# design.net
KiCad netlist of a schematic drawn in Altium Designer
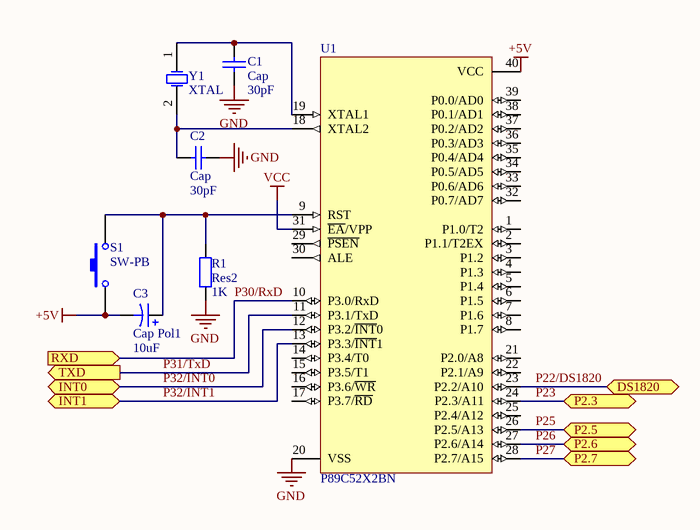
[diagram p0: 最小系统.SchDoc]

(export (version "E")
  (design (tool "Eeschema 10.0.6"))
  (components
    (comp (ref "C1")
      (value "Cap")
      (footprint "RAD-0.3")
      (description "Capacitor")
      (fields (field (name "ALTIUM_VALUE") "30pF") (field (name "PUBLISHER") "Altium Limited"))
      (libsource (lib "Miscellaneous Devices") (part "Cap"))
    )
    (comp (ref "C2")
      (value "Cap")
      (footprint "RAD-0.3")
      (description "Capacitor")
      (fields (field (name "ALTIUM_VALUE") "30pF") (field (name "PUBLISHER") "Altium Limited"))
      (libsource (lib "Miscellaneous Devices") (part "Cap"))
    )
    (comp (ref "C3")
      (value "Cap Pol1")
      (footprint "RB7.6-15")
      (description "Polarized Capacitor (Radial)")
      (fields (field (name "ALTIUM_VALUE") "10uF") (field (name "PUBLISHER") "Altium Limited"))
      (libsource (lib "Miscellaneous Devices") (part "Cap Pol1"))
    )
    (comp (ref "R1")
      (value "Res2")
      (footprint "AXIAL-0.4")
      (description "Resistor")
      (fields (field (name "ALTIUM_VALUE") "1K") (field (name "PUBLISHER") "Altium Limited"))
      (libsource (lib "Miscellaneous Devices") (part "Res2"))
    )
    (comp (ref "S1")
      (value "SW-PB")
      (footprint "SPST-2")
      (description "Switch")
      (fields (field (name "PUBLISHER") "Altium Limited"))
      (libsource (lib "Miscellaneous Devices") (part "SW-PB"))
    )
    (comp (ref "U1")
      (value "P89C52X2BN")
      (footprint "SOT129-1")
      (description "80C51 8-Bit Flash Microcontroller Family, 8 kB Flash")
      (fields (field (name "PUBLISHER") "Altium Limited"))
      (libsource (lib "Philips Microcontroller 8-Bit") (part "P89C52X2BN"))
    )
    (comp (ref "Y1")
      (value "XTAL")
      (footprint "R38")
      (description "Crystal Oscillator")
      (fields (field (name "PUBLISHER") "Altium Limited"))
      (libsource (lib "Miscellaneous Devices") (part "XTAL"))
    )
  )
  (nets
    (net (code "1") (name "+5V") (class "Default")
      (node (ref "C3") (pin "2") (pinfunction "2_2") (pintype "passive"))
      (node (ref "S1") (pin "1") (pinfunction "1_1") (pintype "passive"))
      (node (ref "U1") (pin "40") (pinfunction "VCC_40") (pintype "power_in"))
    )
    (net (code "2") (name "/P22{slash}DS1820") (class "Default")
      (node (ref "U1") (pin "23") (pinfunction "P2.2/A10_23") (pintype "bidirectional"))
    )
    (net (code "3") (name "/P23") (class "Default")
      (node (ref "U1") (pin "24") (pinfunction "P2.3/A11_24") (pintype "bidirectional"))
    )
    (net (code "4") (name "/P25") (class "Default")
      (node (ref "U1") (pin "26") (pinfunction "P2.5/A13_26") (pintype "bidirectional"))
    )
    (net (code "5") (name "/P26") (class "Default")
      (node (ref "U1") (pin "27") (pinfunction "P2.6/A14_27") (pintype "bidirectional"))
    )
    (net (code "6") (name "/P27") (class "Default")
      (node (ref "U1") (pin "28") (pinfunction "P2.7/A15_28") (pintype "bidirectional"))
    )
    (net (code "7") (name "/P30{slash}RxD") (class "Default")
      (node (ref "U1") (pin "10") (pinfunction "P3.0/RxD_10") (pintype "bidirectional"))
    )
    (net (code "8") (name "/P31{slash}TxD") (class "Default")
      (node (ref "U1") (pin "11") (pinfunction "P3.1/TxD_11") (pintype "bidirectional"))
    )
    (net (code "9") (name "/P32{slash}INT0") (class "Default")
      (node (ref "U1") (pin "12") (pinfunction "P3.2/~{INT}0_12") (pintype "bidirectional"))
    )
    (net (code "10") (name "/P32{slash}INT1") (class "Default")
      (node (ref "U1") (pin "13") (pinfunction "P3.3/~{INT}1_13") (pintype "bidirectional"))
    )
    (net (code "11") (name "GND") (class "Default")
      (node (ref "C1") (pin "1") (pinfunction "1_1") (pintype "passive"))
      (node (ref "C2") (pin "1") (pinfunction "1_1") (pintype "passive"))
      (node (ref "R1") (pin "1") (pinfunction "1_1") (pintype "passive"))
      (node (ref "U1") (pin "20") (pinfunction "VSS_20") (pintype "power_in"))
    )
    (net (code "12") (name "Net-(U1-RST)") (class "Default")
      (node (ref "C3") (pin "1") (pinfunction "1_1") (pintype "passive"))
      (node (ref "R1") (pin "2") (pinfunction "2_2") (pintype "passive"))
      (node (ref "S1") (pin "2") (pinfunction "2_2") (pintype "passive"))
      (node (ref "U1") (pin "9") (pinfunction "RST_9") (pintype "input"))
    )
    (net (code "13") (name "Net-(U1-XTAL1)") (class "Default")
      (node (ref "C1") (pin "2") (pinfunction "2_2") (pintype "passive"))
      (node (ref "U1") (pin "19") (pinfunction "XTAL1_19") (pintype "input"))
      (node (ref "Y1") (pin "1") (pinfunction "OSC1_1") (pintype "passive"))
    )
    (net (code "14") (name "Net-(U1-XTAL2)") (class "Default")
      (node (ref "C2") (pin "2") (pinfunction "2_2") (pintype "passive"))
      (node (ref "U1") (pin "18") (pinfunction "XTAL2_18") (pintype "output"))
      (node (ref "Y1") (pin "2") (pinfunction "OSC2_2") (pintype "passive"))
    )
    (net (code "15") (name "VCC") (class "Default")
      (node (ref "U1") (pin "31") (pinfunction "~{EA}/VPP_31") (pintype "input"))
    )
    (net (code "16") (name "unconnected-(U1-ALE-Pad30)") (class "Default")
      (node (ref "U1") (pin "30") (pinfunction "ALE_30") (pintype "output"))
    )
    (net (code "17") (name "unconnected-(U1-P0.0{slash}AD0-Pad39)") (class "Default")
      (node (ref "U1") (pin "39") (pinfunction "P0.0/AD0_39") (pintype "bidirectional"))
    )
    (net (code "18") (name "unconnected-(U1-P0.1{slash}AD1-Pad38)") (class "Default")
      (node (ref "U1") (pin "38") (pinfunction "P0.1/AD1_38") (pintype "bidirectional"))
    )
    (net (code "19") (name "unconnected-(U1-P0.2{slash}AD2-Pad37)") (class "Default")
      (node (ref "U1") (pin "37") (pinfunction "P0.2/AD2_37") (pintype "bidirectional"))
    )
    (net (code "20") (name "unconnected-(U1-P0.3{slash}AD3-Pad36)") (class "Default")
      (node (ref "U1") (pin "36") (pinfunction "P0.3/AD3_36") (pintype "bidirectional"))
    )
    (net (code "21") (name "unconnected-(U1-P0.4{slash}AD4-Pad35)") (class "Default")
      (node (ref "U1") (pin "35") (pinfunction "P0.4/AD4_35") (pintype "bidirectional"))
    )
    (net (code "22") (name "unconnected-(U1-P0.5{slash}AD5-Pad34)") (class "Default")
      (node (ref "U1") (pin "34") (pinfunction "P0.5/AD5_34") (pintype "bidirectional"))
    )
    (net (code "23") (name "unconnected-(U1-P0.6{slash}AD6-Pad33)") (class "Default")
      (node (ref "U1") (pin "33") (pinfunction "P0.6/AD6_33") (pintype "bidirectional"))
    )
    (net (code "24") (name "unconnected-(U1-P0.7{slash}AD7-Pad32)") (class "Default")
      (node (ref "U1") (pin "32") (pinfunction "P0.7/AD7_32") (pintype "bidirectional"))
    )
    (net (code "25") (name "unconnected-(U1-P1.0{slash}T2-Pad1)") (class "Default")
      (node (ref "U1") (pin "1") (pinfunction "P1.0/T2_1") (pintype "bidirectional"))
    )
    (net (code "26") (name "unconnected-(U1-P1.1{slash}T2EX-Pad2)") (class "Default")
      (node (ref "U1") (pin "2") (pinfunction "P1.1/T2EX_2") (pintype "bidirectional"))
    )
    (net (code "27") (name "unconnected-(U1-P1.2-Pad3)") (class "Default")
      (node (ref "U1") (pin "3") (pinfunction "P1.2_3") (pintype "bidirectional"))
    )
    (net (code "28") (name "unconnected-(U1-P1.3-Pad4)") (class "Default")
      (node (ref "U1") (pin "4") (pinfunction "P1.3_4") (pintype "bidirectional"))
    )
    (net (code "29") (name "unconnected-(U1-P1.4-Pad5)") (class "Default")
      (node (ref "U1") (pin "5") (pinfunction "P1.4_5") (pintype "bidirectional"))
    )
    (net (code "30") (name "unconnected-(U1-P1.5-Pad6)") (class "Default")
      (node (ref "U1") (pin "6") (pinfunction "P1.5_6") (pintype "bidirectional"))
    )
    (net (code "31") (name "unconnected-(U1-P1.6-Pad7)") (class "Default")
      (node (ref "U1") (pin "7") (pinfunction "P1.6_7") (pintype "bidirectional"))
    )
    (net (code "32") (name "unconnected-(U1-P1.7-Pad8)") (class "Default")
      (node (ref "U1") (pin "8") (pinfunction "P1.7_8") (pintype "bidirectional"))
    )
    (net (code "33") (name "unconnected-(U1-P2.0{slash}A8-Pad21)") (class "Default")
      (node (ref "U1") (pin "21") (pinfunction "P2.0/A8_21") (pintype "bidirectional"))
    )
    (net (code "34") (name "unconnected-(U1-P2.1{slash}A9-Pad22)") (class "Default")
      (node (ref "U1") (pin "22") (pinfunction "P2.1/A9_22") (pintype "bidirectional"))
    )
    (net (code "35") (name "unconnected-(U1-P2.4{slash}A12-Pad25)") (class "Default")
      (node (ref "U1") (pin "25") (pinfunction "P2.4/A12_25") (pintype "bidirectional"))
    )
    (net (code "36") (name "unconnected-(U1-P3.4{slash}T0-Pad14)") (class "Default")
      (node (ref "U1") (pin "14") (pinfunction "P3.4/T0_14") (pintype "bidirectional"))
    )
    (net (code "37") (name "unconnected-(U1-P3.5{slash}T1-Pad15)") (class "Default")
      (node (ref "U1") (pin "15") (pinfunction "P3.5/T1_15") (pintype "bidirectional"))
    )
    (net (code "38") (name "unconnected-(U1-P3.6{slash}~{WR}-Pad16)") (class "Default")
      (node (ref "U1") (pin "16") (pinfunction "P3.6/~{WR}_16") (pintype "bidirectional"))
    )
    (net (code "39") (name "unconnected-(U1-P3.7{slash}~{RD}-Pad17)") (class "Default")
      (node (ref "U1") (pin "17") (pinfunction "P3.7/~{RD}_17") (pintype "bidirectional"))
    )
    (net (code "40") (name "unconnected-(U1-~{PSEN}-Pad29)") (class "Default")
      (node (ref "U1") (pin "29") (pinfunction "~{PSEN}_29") (pintype "output"))
    )
  )
)
